# SCH_RP2040_Ucompute_V1_2_2025-10-13.net
KiCad netlist of a schematic drawn in EasyEDA
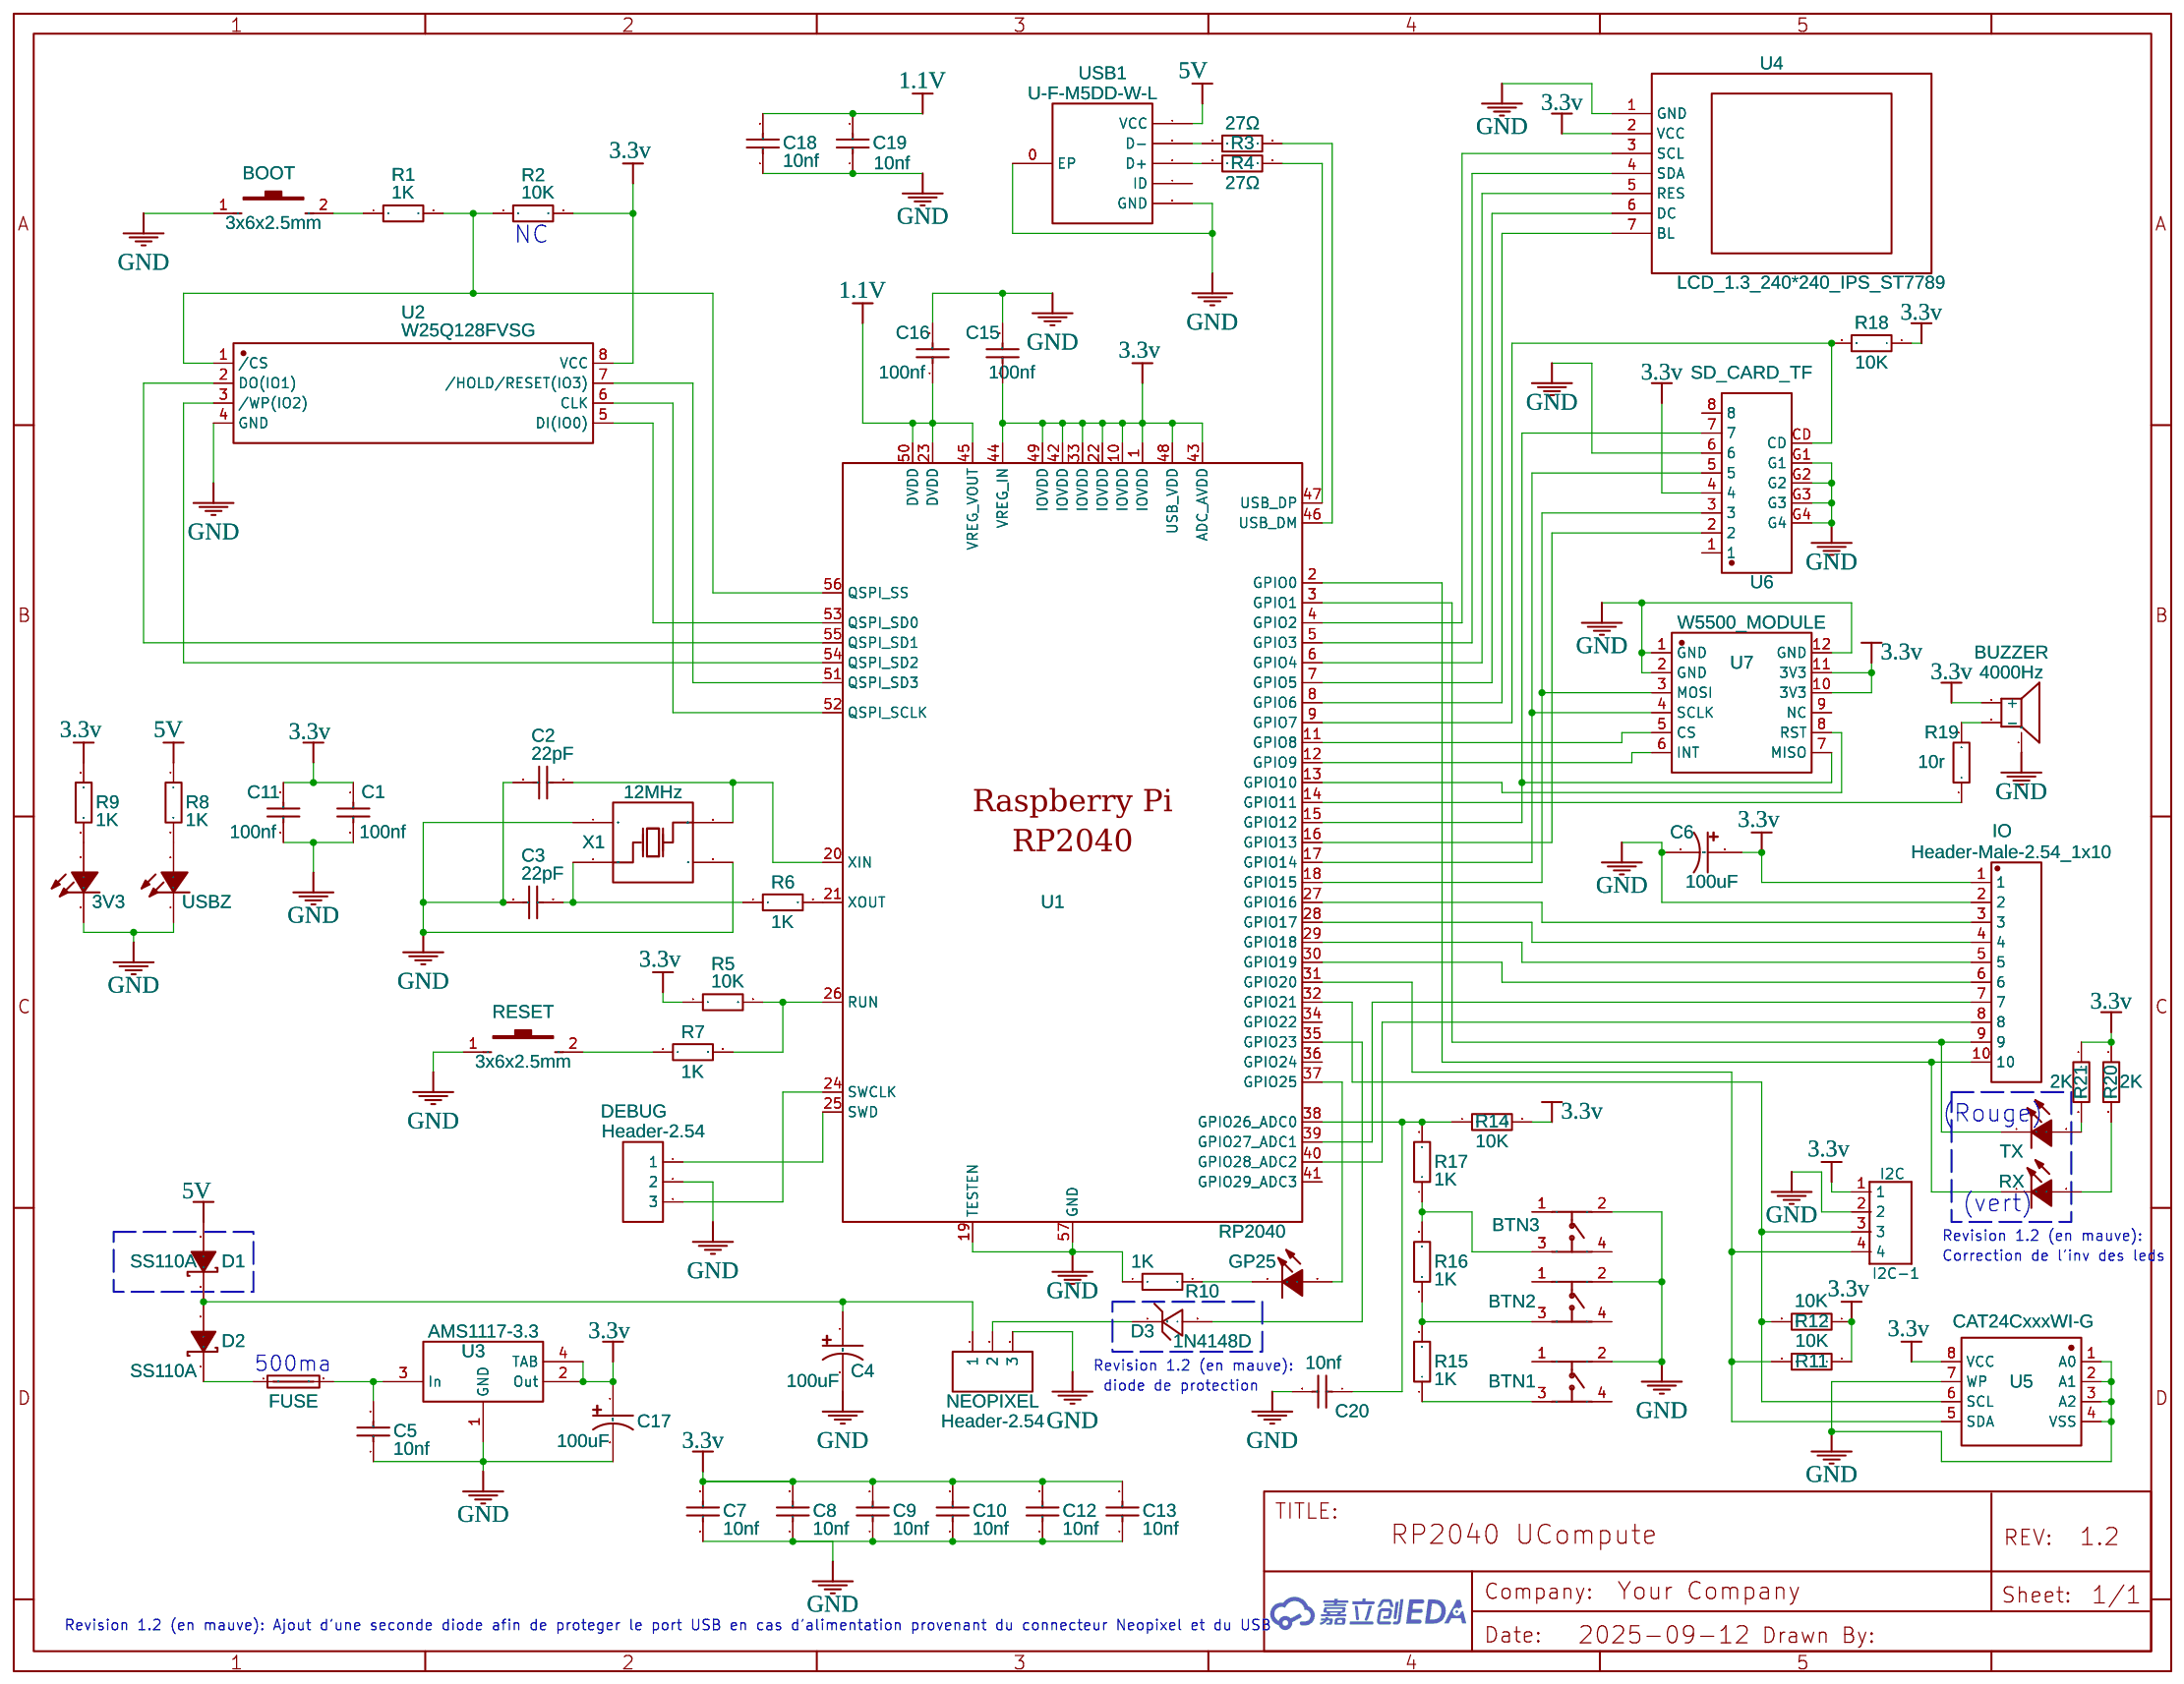
[diagram p0: schematic sheet]

(export (version "E")
  (design (tool "Eeschema 10.0.6"))
  (components
    (comp (ref "3V3")
      (value "XL-1206QPC")
      (fields (field (name "Manufacturer") "LCSC"))
      (libsource (lib "") (part "XL-1206QPC"))
    )
    (comp (ref "BOOT")
      (value "3x6x2.5mm")
      (fields (field (name "Manufacturer") "ReliaPro"))
      (libsource (lib "") (part "3x6x2.5mm_1"))
    )
    (comp (ref "BTN1")
      (value "TC-1102-A-J-R")
      (fields (field (name "Manufacturer") "XKB Connectivity(中国星坤)"))
      (libsource (lib "") (part "TC-1102-A-J-R"))
    )
    (comp (ref "BTN2")
      (value "TC-1102-A-J-R")
      (fields (field (name "Manufacturer") "XKB Connectivity(中国星坤)"))
      (libsource (lib "") (part "TC-1102-A-J-R"))
    )
    (comp (ref "BTN3")
      (value "TC-1102-A-J-R")
      (fields (field (name "Manufacturer") "XKB Connectivity(中国星坤)"))
      (libsource (lib "") (part "TC-1102-A-J-R"))
    )
    (comp (ref "BUZZER")
      (value "4000Hz")
      (fields (field (name "Manufacturer Part") "MLT-5030") (field (name "Manufacturer") "华能"))
      (libsource (lib "") (part "MLT-5030"))
    )
    (comp (ref "C1")
      (value "100nf")
      (fields (field (name "Manufacturer Part") "0805CG220J500NT") (field (name "Manufacturer") "FH"))
      (libsource (lib "") (part "0805CG220J500NT_1"))
    )
    (comp (ref "C2")
      (value "22pF")
      (fields (field (name "Manufacturer Part") "0805CG220J500NT") (field (name "Manufacturer") "FH"))
      (libsource (lib "") (part "0805CG220J500NT_3"))
    )
    (comp (ref "C3")
      (value "22pF")
      (fields (field (name "Manufacturer Part") "0805CG220J500NT") (field (name "Manufacturer") "FH"))
      (libsource (lib "") (part "0805CG220J500NT_3"))
    )
    (comp (ref "C4")
      (value "100uF")
      (fields
        (field (name "Manufacturer Part") "TLJA107M010R1400")
        (field (name "Manufacturer") "Kyocera AVX")
      )
      (libsource (lib "") (part "TLJA107M010R1400_1"))
    )
    (comp (ref "C5")
      (value "10nf")
      (fields (field (name "Manufacturer Part") "0805CG220J500NT") (field (name "Manufacturer") "FH"))
      (libsource (lib "") (part "0805CG220J500NT"))
    )
    (comp (ref "C6")
      (value "100uF")
      (fields
        (field (name "Manufacturer Part") "TLJA107M010R1400")
        (field (name "Manufacturer") "Kyocera AVX")
      )
      (libsource (lib "") (part "TLJA107M010R1400"))
    )
    (comp (ref "C7")
      (value "10nf")
      (fields (field (name "Manufacturer Part") "0805CG220J500NT") (field (name "Manufacturer") "FH"))
      (libsource (lib "") (part "0805CG220J500NT"))
    )
    (comp (ref "C8")
      (value "10nf")
      (fields (field (name "Manufacturer Part") "0805CG220J500NT") (field (name "Manufacturer") "FH"))
      (libsource (lib "") (part "0805CG220J500NT"))
    )
    (comp (ref "C9")
      (value "10nf")
      (fields (field (name "Manufacturer Part") "0805CG220J500NT") (field (name "Manufacturer") "FH"))
      (libsource (lib "") (part "0805CG220J500NT"))
    )
    (comp (ref "C10")
      (value "10nf")
      (fields (field (name "Manufacturer Part") "0805CG220J500NT") (field (name "Manufacturer") "FH"))
      (libsource (lib "") (part "0805CG220J500NT"))
    )
    (comp (ref "C11")
      (value "100nf")
      (fields (field (name "Manufacturer Part") "0805CG220J500NT") (field (name "Manufacturer") "FH"))
      (libsource (lib "") (part "0805CG220J500NT"))
    )
    (comp (ref "C12")
      (value "10nf")
      (fields (field (name "Manufacturer Part") "0805CG220J500NT") (field (name "Manufacturer") "FH"))
      (libsource (lib "") (part "0805CG220J500NT"))
    )
    (comp (ref "C13")
      (value "10nf")
      (fields (field (name "Manufacturer Part") "0805CG220J500NT") (field (name "Manufacturer") "FH"))
      (libsource (lib "") (part "0805CG220J500NT"))
    )
    (comp (ref "C15")
      (value "100nf")
      (fields (field (name "Manufacturer Part") "0805CG220J500NT") (field (name "Manufacturer") "FH"))
      (libsource (lib "") (part "0805CG220J500NT"))
    )
    (comp (ref "C16")
      (value "100nf")
      (fields (field (name "Manufacturer Part") "0805CG220J500NT") (field (name "Manufacturer") "FH"))
      (libsource (lib "") (part "0805CG220J500NT"))
    )
    (comp (ref "C17")
      (value "100uF")
      (fields
        (field (name "Manufacturer Part") "TLJA107M010R1400")
        (field (name "Manufacturer") "Kyocera AVX")
      )
      (libsource (lib "") (part "TLJA107M010R1400_1"))
    )
    (comp (ref "C18")
      (value "10nf")
      (fields (field (name "Manufacturer Part") "0805CG220J500NT") (field (name "Manufacturer") "FH"))
      (libsource (lib "") (part "0805CG220J500NT"))
    )
    (comp (ref "C19")
      (value "10nf")
      (fields (field (name "Manufacturer Part") "0805CG220J500NT") (field (name "Manufacturer") "FH"))
      (libsource (lib "") (part "0805CG220J500NT"))
    )
    (comp (ref "C20")
      (value "10nf")
      (fields (field (name "Manufacturer Part") "0805CG220J500NT") (field (name "Manufacturer") "FH"))
      (libsource (lib "") (part "0805CG220J500NT_2"))
    )
    (comp (ref "D1")
      (value "SS110A")
      (fields (field (name "Manufacturer") "Yangzhou Yangjie Elec Tech"))
      (libsource (lib "") (part "SS110A"))
    )
    (comp (ref "D2")
      (value "SS110A")
      (fields (field (name "Manufacturer") "Yangzhou Yangjie Elec Tech"))
      (libsource (lib "") (part "SS110A"))
    )
    (comp (ref "D3") (value "1N4148D") (libsource (lib "") (part "1N4148D")))
    (comp (ref "DEBUG")
      (value "Header-2.54")
      (fields (field (name "Manufacturer Part") "2.54-1*3P针") (field (name "Manufacturer") "BOOMELE(博穆精密)"))
      (libsource (lib "") (part "Header-Male-2.54_1x3"))
    )
    (comp (ref "FUSE")
      (value "FUSE1206")
      (fields (field (name "Manufacturer Part") "D22051903536_fuse1206"))
      (libsource (lib "") (part "D22051903536_FUSE1206"))
    )
    (comp (ref "GP25")
      (value "XL-1206QPC")
      (fields (field (name "Manufacturer") "LCSC"))
      (libsource (lib "") (part "XL-1206QPC_4"))
    )
    (comp (ref "I2C-1") (value "I2C") (libsource (lib "") (part "Unknown_941_-225")))
    (comp (ref "IO")
      (value "Header-Male-2.54_1x10")
      (fields (field (name "Manufacturer Part") "2.54-1*10P针") (field (name "Manufacturer") "BOOMELE(博穆精密)"))
      (libsource (lib "") (part "Header-Male-2.54_1x10"))
    )
    (comp (ref "NEOPIXEL")
      (value "Header-2.54")
      (fields (field (name "Manufacturer Part") "2.54-1*3P针") (field (name "Manufacturer") "BOOMELE(博穆精密)"))
      (libsource (lib "") (part "Header-Male-2.54_1x3_1"))
    )
    (comp (ref "R1")
      (value "1K")
      (fields (field (name "Manufacturer Part") "RC0805DR-071KL") (field (name "Manufacturer") "YAGEO(国巨)"))
      (libsource (lib "") (part "RC0805DR-071KL_2"))
    )
    (comp (ref "R2")
      (value "10K")
      (fields (field (name "Manufacturer Part") "RC0805DR-071KL") (field (name "Manufacturer") "YAGEO(国巨)"))
      (libsource (lib "") (part "RC0805DR-071KL_2"))
    )
    (comp (ref "R3")
      (value "27Ω")
      (fields (field (name "Manufacturer Part") "RC0805DR-071KL") (field (name "Manufacturer") "YAGEO(国巨)"))
      (libsource (lib "") (part "RC0805DR-071KL_2"))
    )
    (comp (ref "R4")
      (value "27Ω")
      (fields (field (name "Manufacturer Part") "RC0805DR-071KL") (field (name "Manufacturer") "YAGEO(国巨)"))
      (libsource (lib "") (part "RC0805DR-071KL_2"))
    )
    (comp (ref "R5")
      (value "10K")
      (fields (field (name "Manufacturer Part") "RC0805DR-071KL") (field (name "Manufacturer") "YAGEO(国巨)"))
      (libsource (lib "") (part "RC0805DR-071KL_2"))
    )
    (comp (ref "R6")
      (value "1K")
      (fields (field (name "Manufacturer Part") "RC0805DR-071KL") (field (name "Manufacturer") "YAGEO(国巨)"))
      (libsource (lib "") (part "RC0805DR-071KL_2"))
    )
    (comp (ref "R7")
      (value "1K")
      (fields (field (name "Manufacturer Part") "RC0805DR-071KL") (field (name "Manufacturer") "YAGEO(国巨)"))
      (libsource (lib "") (part "RC0805DR-071KL_2"))
    )
    (comp (ref "R8")
      (value "1K")
      (fields (field (name "Manufacturer Part") "RC0805DR-071KL") (field (name "Manufacturer") "YAGEO(国巨)"))
      (libsource (lib "") (part "RC0805DR-071KL_3"))
    )
    (comp (ref "R9")
      (value "1K")
      (fields (field (name "Manufacturer Part") "RC0805DR-071KL") (field (name "Manufacturer") "YAGEO(国巨)"))
      (libsource (lib "") (part "RC0805DR-071KL_3"))
    )
    (comp (ref "R10")
      (value "1K")
      (fields (field (name "Manufacturer Part") "RC0805DR-071KL") (field (name "Manufacturer") "YAGEO(国巨)"))
      (libsource (lib "") (part "RC0805DR-071KL_2"))
    )
    (comp (ref "R11")
      (value "10K")
      (fields (field (name "Manufacturer Part") "RC0805DR-071KL") (field (name "Manufacturer") "YAGEO(国巨)"))
      (libsource (lib "") (part "RC0805DR-071KL_1"))
    )
    (comp (ref "R12")
      (value "10K")
      (fields (field (name "Manufacturer Part") "RC0805DR-071KL") (field (name "Manufacturer") "YAGEO(国巨)"))
      (libsource (lib "") (part "RC0805DR-071KL_1"))
    )
    (comp (ref "R14")
      (value "10K")
      (fields (field (name "Manufacturer Part") "RC0805DR-071KL") (field (name "Manufacturer") "YAGEO(国巨)"))
      (libsource (lib "") (part "RC0805DR-071KL_2"))
    )
    (comp (ref "R15")
      (value "1K")
      (fields (field (name "Manufacturer Part") "RC0805DR-071KL") (field (name "Manufacturer") "YAGEO(国巨)"))
      (libsource (lib "") (part "RC0805DR-071KL"))
    )
    (comp (ref "R16")
      (value "1K")
      (fields (field (name "Manufacturer Part") "RC0805DR-071KL") (field (name "Manufacturer") "YAGEO(国巨)"))
      (libsource (lib "") (part "RC0805DR-071KL"))
    )
    (comp (ref "R17")
      (value "1K")
      (fields (field (name "Manufacturer Part") "RC0805DR-071KL") (field (name "Manufacturer") "YAGEO(国巨)"))
      (libsource (lib "") (part "RC0805DR-071KL"))
    )
    (comp (ref "R18")
      (value "10K")
      (fields (field (name "Manufacturer Part") "RC0805DR-071KL") (field (name "Manufacturer") "YAGEO(国巨)"))
      (libsource (lib "") (part "RC0805DR-071KL_1"))
    )
    (comp (ref "R19")
      (value "10r")
      (fields (field (name "Manufacturer Part") "RC0805DR-071KL") (field (name "Manufacturer") "YAGEO(国巨)"))
      (libsource (lib "") (part "RC0805DR-071KL"))
    )
    (comp (ref "R20")
      (value "2K")
      (fields (field (name "Manufacturer Part") "RC0805DR-071KL") (field (name "Manufacturer") "YAGEO(国巨)"))
      (libsource (lib "") (part "RC0805DR-071KL_3"))
    )
    (comp (ref "R21")
      (value "2K")
      (fields (field (name "Manufacturer Part") "RC0805DR-071KL") (field (name "Manufacturer") "YAGEO(国巨)"))
      (libsource (lib "") (part "RC0805DR-071KL_3"))
    )
    (comp (ref "RESET")
      (value "3x6x2.5mm")
      (fields (field (name "Manufacturer") "ReliaPro"))
      (libsource (lib "") (part "3x6x2.5mm"))
    )
    (comp (ref "RX1")
      (value "RX")
      (fields (field (name "Manufacturer Part") "XL-1206QPC") (field (name "Manufacturer") "LCSC"))
      (libsource (lib "") (part "XL-1206QPC_1"))
    )
    (comp (ref "TX1")
      (value "TX")
      (fields (field (name "Manufacturer Part") "XL-1206QPC") (field (name "Manufacturer") "LCSC"))
      (libsource (lib "") (part "XL-1206QPC_3"))
    )
    (comp (ref "U1")
      (value "RP2040")
      (fields (field (name "Manufacturer") "Raspberry Pi(树莓派)"))
      (libsource (lib "") (part "RP2040"))
    )
    (comp (ref "U2") (value "W25Q128FVSG") (libsource (lib "") (part "W25Q128FVSG")))
    (comp (ref "U3")
      (value "AMS1117-3.3")
      (fields (field (name "Manufacturer Part") "AMS1117-5.0") (field (name "Manufacturer") "SK"))
      (libsource (lib "") (part "AMS1117-5.0_C165483"))
    )
    (comp (ref "U4")
      (value "LCD_1.3_240*240_IPS_ST7789")
      (libsource (lib "") (part "LCD_1.3_240*240_IPS_ST7789"))
    )
    (comp (ref "U5") (value "CAT24CxxxWI-G") (libsource (lib "") (part "CAT24C256WI-G")))
    (comp (ref "U6")
      (value "SD_CARD_TF")
      (fields (field (name "Manufacturer Part") "SD_Card_TF"))
      (libsource (lib "") (part "SD_CARD_TF"))
    )
    (comp (ref "U7") (value "W5500_MODULE") (libsource (lib "") (part "W5500_MODULE")))
    (comp (ref "USB1")
      (value "U-F-M5DD-W-L")
      (fields (field (name "Manufacturer") "韩国韩荣"))
      (libsource (lib "") (part "U-F-M5DD-W-L"))
    )
    (comp (ref "USBZ")
      (value "XL-1206QPC")
      (fields (field (name "Manufacturer") "LCSC"))
      (libsource (lib "") (part "XL-1206QPC_2"))
    )
    (comp (ref "X1")
      (value "12MHz")
      (fields
        (field (name "Manufacturer Part") "TSX-3225 12MHz 20pF 30ppm")
        (field (name "Manufacturer") "EPSON")
      )
      (libsource (lib "") (part "TSX-3225 12MHz 20pF 30ppm"))
    )
  )
  (nets
    (net (code "1") (name "1.1V") (class "Default")
      (node (ref "C16") (pin "1") (pinfunction "1_1") (pintype "input"))
      (node (ref "C18") (pin "2") (pinfunction "2_2") (pintype "input"))
      (node (ref "C19") (pin "2") (pinfunction "2_2") (pintype "input"))
      (node (ref "U1") (pin "23") (pinfunction "DVDD_23") (pintype "bidirectional"))
      (node (ref "U1") (pin "45") (pinfunction "VREG_VOUT_45") (pintype "bidirectional"))
      (node (ref "U1") (pin "50") (pinfunction "DVDD_50") (pintype "bidirectional"))
    )
    (net (code "2") (name "3.3v") (class "Default")
      (node (ref "BUZZER") (pin "2") (pinfunction "+_2") (pintype "unspecified"))
      (node (ref "C1") (pin "1") (pinfunction "1_1") (pintype "input"))
      (node (ref "C10") (pin "2") (pinfunction "2_2") (pintype "input"))
      (node (ref "C11") (pin "2") (pinfunction "2_2") (pintype "input"))
      (node (ref "C12") (pin "2") (pinfunction "2_2") (pintype "input"))
      (node (ref "C13") (pin "2") (pinfunction "2_2") (pintype "input"))
      (node (ref "C15") (pin "1") (pinfunction "1_1") (pintype "input"))
      (node (ref "C17") (pin "1") (pinfunction "1_1") (pintype "unspecified"))
      (node (ref "C6") (pin "1") (pinfunction "1_1") (pintype "unspecified"))
      (node (ref "C7") (pin "2") (pinfunction "2_2") (pintype "input"))
      (node (ref "C8") (pin "2") (pinfunction "2_2") (pintype "input"))
      (node (ref "C9") (pin "2") (pinfunction "2_2") (pintype "input"))
      (node (ref "I2C-1") (pin "1") (pinfunction "1_1") (pintype "bidirectional"))
      (node (ref "IO") (pin "1") (pinfunction "1_1") (pintype "unspecified"))
      (node (ref "R11") (pin "1") (pinfunction "1_1") (pintype "unspecified"))
      (node (ref "R12") (pin "1") (pinfunction "1_1") (pintype "unspecified"))
      (node (ref "R14") (pin "2") (pinfunction "2_2") (pintype "unspecified"))
      (node (ref "R18") (pin "1") (pinfunction "1_1") (pintype "unspecified"))
      (node (ref "R2") (pin "2") (pinfunction "2_2") (pintype "unspecified"))
      (node (ref "R20") (pin "1") (pinfunction "1_1") (pintype "unspecified"))
      (node (ref "R21") (pin "1") (pinfunction "1_1") (pintype "unspecified"))
      (node (ref "R5") (pin "1") (pinfunction "1_1") (pintype "unspecified"))
      (node (ref "R9") (pin "1") (pinfunction "1_1") (pintype "unspecified"))
      (node (ref "U1") (pin "1") (pinfunction "IOVDD_1") (pintype "bidirectional"))
      (node (ref "U1") (pin "10") (pinfunction "IOVDD_10") (pintype "bidirectional"))
      (node (ref "U1") (pin "22") (pinfunction "IOVDD_22") (pintype "bidirectional"))
      (node (ref "U1") (pin "33") (pinfunction "IOVDD_33") (pintype "bidirectional"))
      (node (ref "U1") (pin "42") (pinfunction "IOVDD_42") (pintype "bidirectional"))
      (node (ref "U1") (pin "43") (pinfunction "ADC_AVDD_43") (pintype "bidirectional"))
      (node (ref "U1") (pin "44") (pinfunction "VREG_IN_44") (pintype "bidirectional"))
      (node (ref "U1") (pin "48") (pinfunction "USB_VDD_48") (pintype "bidirectional"))
      (node (ref "U1") (pin "49") (pinfunction "IOVDD_49") (pintype "bidirectional"))
      (node (ref "U2") (pin "8") (pinfunction "VCC_8") (pintype "unspecified"))
      (node (ref "U3") (pin "2") (pinfunction "Out_2") (pintype "unspecified"))
      (node (ref "U3") (pin "4") (pinfunction "TAB_4") (pintype "unspecified"))
      (node (ref "U4") (pin "2") (pinfunction "VCC_2") (pintype "unspecified"))
      (node (ref "U5") (pin "8") (pinfunction "VCC_8") (pintype "unspecified"))
      (node (ref "U6") (pin "4") (pinfunction "4_4") (pintype "unspecified"))
      (node (ref "U7") (pin "10") (pinfunction "3V3_10") (pintype "unspecified"))
      (node (ref "U7") (pin "11") (pinfunction "3V3_11") (pintype "unspecified"))
    )
    (net (code "3") (name "5V") (class "Default")
      (node (ref "D2") (pin "2") (pinfunction "A_2") (pintype "unspecified"))
      (node (ref "R8") (pin "1") (pinfunction "1_1") (pintype "unspecified"))
      (node (ref "USB1") (pin "1") (pinfunction "VCC_1") (pintype "input"))
    )
    (net (code "4") (name "GND") (class "Default")
      (node (ref "3V3") (pin "1") (pinfunction "K_1") (pintype "unspecified"))
      (node (ref "BOOT") (pin "1") (pinfunction "1_1") (pintype "input"))
      (node (ref "BTN1") (pin "2") (pinfunction "2_2") (pintype "unspecified"))
      (node (ref "BTN2") (pin "2") (pinfunction "2_2") (pintype "unspecified"))
      (node (ref "BTN3") (pin "2") (pinfunction "2_2") (pintype "unspecified"))
      (node (ref "BUZZER") (pin "1") (pinfunction "NC_1") (pintype "unspecified"))
      (node (ref "C1") (pin "2") (pinfunction "2_2") (pintype "input"))
      (node (ref "C10") (pin "1") (pinfunction "1_1") (pintype "input"))
      (node (ref "C11") (pin "1") (pinfunction "1_1") (pintype "input"))
      (node (ref "C12") (pin "1") (pinfunction "1_1") (pintype "input"))
      (node (ref "C13") (pin "1") (pinfunction "1_1") (pintype "input"))
      (node (ref "C15") (pin "2") (pinfunction "2_2") (pintype "input"))
      (node (ref "C16") (pin "2") (pinfunction "2_2") (pintype "input"))
      (node (ref "C17") (pin "2") (pinfunction "2_2") (pintype "unspecified"))
      (node (ref "C18") (pin "1") (pinfunction "1_1") (pintype "input"))
      (node (ref "C19") (pin "1") (pinfunction "1_1") (pintype "input"))
      (node (ref "C2") (pin "1") (pinfunction "1_1") (pintype "input"))
      (node (ref "C20") (pin "2") (pinfunction "2_2") (pintype "input"))
      (node (ref "C3") (pin "1") (pinfunction "1_1") (pintype "input"))
      (node (ref "C4") (pin "2") (pinfunction "2_2") (pintype "unspecified"))
      (node (ref "C5") (pin "1") (pinfunction "1_1") (pintype "input"))
      (node (ref "C6") (pin "2") (pinfunction "2_2") (pintype "unspecified"))
      (node (ref "C7") (pin "1") (pinfunction "1_1") (pintype "input"))
      (node (ref "C8") (pin "1") (pinfunction "1_1") (pintype "input"))
      (node (ref "C9") (pin "1") (pinfunction "1_1") (pintype "input"))
      (node (ref "DEBUG") (pin "2") (pinfunction "2_2") (pintype "input"))
      (node (ref "I2C-1") (pin "2") (pinfunction "2_2") (pintype "bidirectional"))
      (node (ref "IO") (pin "2") (pinfunction "2_2") (pintype "unspecified"))
      (node (ref "NEOPIXEL") (pin "3") (pinfunction "3_3") (pintype "input"))
      (node (ref "R10") (pin "1") (pinfunction "1_1") (pintype "unspecified"))
      (node (ref "RESET") (pin "1") (pinfunction "1_1") (pintype "input"))
      (node (ref "U1") (pin "19") (pinfunction "TESTEN_19") (pintype "unspecified"))
      (node (ref "U1") (pin "57") (pinfunction "GND_57") (pintype "bidirectional"))
      (node (ref "U2") (pin "4") (pinfunction "GND_4") (pintype "unspecified"))
      (node (ref "U3") (pin "1") (pinfunction "GND_1") (pintype "unspecified"))
      (node (ref "U4") (pin "1") (pinfunction "GND_1") (pintype "unspecified"))
      (node (ref "U5") (pin "1") (pinfunction "A0_1") (pintype "unspecified"))
      (node (ref "U5") (pin "2") (pinfunction "A1_2") (pintype "unspecified"))
      (node (ref "U5") (pin "3") (pinfunction "A2_3") (pintype "unspecified"))
      (node (ref "U5") (pin "4") (pinfunction "VSS_4") (pintype "unspecified"))
      (node (ref "U5") (pin "7") (pinfunction "WP_7") (pintype "unspecified"))
      (node (ref "U6") (pin "6") (pinfunction "6_6") (pintype "unspecified"))
      (node (ref "U6") (pin "G1") (pinfunction "G1_G1") (pintype "unspecified"))
      (node (ref "U6") (pin "G2") (pinfunction "G2_G2") (pintype "unspecified"))
      (node (ref "U6") (pin "G3") (pinfunction "G3_G3") (pintype "unspecified"))
      (node (ref "U6") (pin "G4") (pinfunction "G4_G4") (pintype "unspecified"))
      (node (ref "U7") (pin "1") (pinfunction "GND_1") (pintype "unspecified"))
      (node (ref "U7") (pin "12") (pinfunction "GND_12") (pintype "unspecified"))
      (node (ref "U7") (pin "2") (pinfunction "GND_2") (pintype "unspecified"))
      (node (ref "USB1") (pin "0") (pinfunction "EP_0") (pintype "unspecified"))
      (node (ref "USB1") (pin "5") (pinfunction "GND_5") (pintype "input"))
      (node (ref "USBZ") (pin "1") (pinfunction "K_1") (pintype "unspecified"))
      (node (ref "X1") (pin "2") (pinfunction "NC_2") (pintype "input"))
      (node (ref "X1") (pin "4") (pinfunction "NC_4") (pintype "input"))
    )
    (net (code "5") (name "Net-(3V3-A)") (class "Default")
      (node (ref "3V3") (pin "2") (pinfunction "A_2") (pintype "unspecified"))
      (node (ref "R9") (pin "2") (pinfunction "2_2") (pintype "unspecified"))
    )
    (net (code "6") (name "Net-(BOOT-Pad2)") (class "Default")
      (node (ref "BOOT") (pin "2") (pinfunction "2_2") (pintype "input"))
      (node (ref "R1") (pin "1") (pinfunction "1_1") (pintype "unspecified"))
    )
    (net (code "7") (name "Net-(BTN1-Pad3)") (class "Default")
      (node (ref "BTN1") (pin "3") (pinfunction "3_3") (pintype "unspecified"))
      (node (ref "R15") (pin "1") (pinfunction "1_1") (pintype "unspecified"))
    )
    (net (code "8") (name "Net-(BTN2-Pad3)") (class "Default")
      (node (ref "BTN2") (pin "3") (pinfunction "3_3") (pintype "unspecified"))
      (node (ref "R15") (pin "2") (pinfunction "2_2") (pintype "unspecified"))
      (node (ref "R16") (pin "1") (pinfunction "1_1") (pintype "unspecified"))
    )
    (net (code "9") (name "Net-(BTN3-Pad3)") (class "Default")
      (node (ref "BTN3") (pin "3") (pinfunction "3_3") (pintype "unspecified"))
      (node (ref "R16") (pin "2") (pinfunction "2_2") (pintype "unspecified"))
      (node (ref "R17") (pin "1") (pinfunction "1_1") (pintype "unspecified"))
    )
    (net (code "10") (name "Net-(BUZZER--)") (class "Default")
      (node (ref "BUZZER") (pin "3") (pinfunction "-_3") (pintype "unspecified"))
      (node (ref "R19") (pin "2") (pinfunction "2_2") (pintype "unspecified"))
    )
    (net (code "11") (name "Net-(D1-A)") (class "Default")
      (node (ref "C4") (pin "1") (pinfunction "1_1") (pintype "unspecified"))
      (node (ref "D1") (pin "2") (pinfunction "A_2") (pintype "unspecified"))
      (node (ref "D2") (pin "1") (pinfunction "K_1") (pintype "unspecified"))
      (node (ref "NEOPIXEL") (pin "1") (pinfunction "1_1") (pintype "input"))
    )
    (net (code "12") (name "Net-(D1-K)") (class "Default")
      (node (ref "D1") (pin "1") (pinfunction "K_1") (pintype "unspecified"))
      (node (ref "FUSE") (pin "1") (pinfunction "1_1") (pintype "unspecified"))
    )
    (net (code "13") (name "Net-(D3-A)") (class "Default")
      (node (ref "D3") (pin "2") (pinfunction "A_2") (pintype "unspecified"))
      (node (ref "U1") (pin "35") (pinfunction "GPIO23_35") (pintype "bidirectional"))
    )
    (net (code "14") (name "Net-(D3-C)") (class "Default")
      (node (ref "D3") (pin "1") (pinfunction "C_1") (pintype "unspecified"))
      (node (ref "NEOPIXEL") (pin "2") (pinfunction "2_2") (pintype "input"))
    )
    (net (code "15") (name "Net-(GP25-A)") (class "Default")
      (node (ref "GP25") (pin "2") (pinfunction "A_2") (pintype "unspecified"))
      (node (ref "U1") (pin "37") (pinfunction "GPIO25_37") (pintype "bidirectional"))
    )
    (net (code "16") (name "Net-(GP25-K)") (class "Default")
      (node (ref "GP25") (pin "1") (pinfunction "K_1") (pintype "unspecified"))
      (node (ref "R10") (pin "2") (pinfunction "2_2") (pintype "unspecified"))
    )
    (net (code "17") (name "Net-(R7-Pad1)") (class "Default")
      (node (ref "R7") (pin "1") (pinfunction "1_1") (pintype "unspecified"))
      (node (ref "RESET") (pin "2") (pinfunction "2_2") (pintype "input"))
    )
    (net (code "18") (name "Net-(RX1-A)") (class "Default")
      (node (ref "R20") (pin "2") (pinfunction "2_2") (pintype "unspecified"))
      (node (ref "RX1") (pin "2") (pinfunction "A_2") (pintype "unspecified"))
    )
    (net (code "19") (name "Net-(RX1-K)") (class "Default")
      (node (ref "IO") (pin "10") (pinfunction "10_10") (pintype "unspecified"))
      (node (ref "RX1") (pin "1") (pinfunction "K_1") (pintype "unspecified"))
      (node (ref "U1") (pin "2") (pinfunction "GPIO0_2") (pintype "bidirectional"))
    )
    (net (code "20") (name "Net-(TX1-A)") (class "Default")
      (node (ref "R21") (pin "2") (pinfunction "2_2") (pintype "unspecified"))
      (node (ref "TX1") (pin "2") (pinfunction "A_2") (pintype "unspecified"))
    )
    (net (code "21") (name "Net-(TX1-K)") (class "Default")
      (node (ref "IO") (pin "9") (pinfunction "9_9") (pintype "unspecified"))
      (node (ref "TX1") (pin "1") (pinfunction "K_1") (pintype "unspecified"))
      (node (ref "U1") (pin "3") (pinfunction "GPIO1_3") (pintype "bidirectional"))
    )
    (net (code "22") (name "Net-(U1-GPIO2)") (class "Default")
      (node (ref "U1") (pin "4") (pinfunction "GPIO2_4") (pintype "bidirectional"))
      (node (ref "U4") (pin "3") (pinfunction "SCL_3") (pintype "unspecified"))
    )
    (net (code "23") (name "Net-(U1-GPIO3)") (class "Default")
      (node (ref "U1") (pin "5") (pinfunction "GPIO3_5") (pintype "bidirectional"))
      (node (ref "U4") (pin "4") (pinfunction "SDA_4") (pintype "unspecified"))
    )
    (net (code "24") (name "Net-(U1-GPIO4)") (class "Default")
      (node (ref "U1") (pin "6") (pinfunction "GPIO4_6") (pintype "bidirectional"))
      (node (ref "U4") (pin "5") (pinfunction "RES_5") (pintype "unspecified"))
    )
    (net (code "25") (name "Net-(U1-GPIO5)") (class "Default")
      (node (ref "U1") (pin "7") (pinfunction "GPIO5_7") (pintype "bidirectional"))
      (node (ref "U4") (pin "6") (pinfunction "DC_6") (pintype "unspecified"))
    )
    (net (code "26") (name "Net-(U1-GPIO6)") (class "Default")
      (node (ref "U1") (pin "8") (pinfunction "GPIO6_8") (pintype "bidirectional"))
      (node (ref "U4") (pin "7") (pinfunction "BL_7") (pintype "unspecified"))
    )
    (net (code "27") (name "Net-(U1-GPIO7)") (class "Default")
      (node (ref "R18") (pin "2") (pinfunction "2_2") (pintype "unspecified"))
      (node (ref "U1") (pin "9") (pinfunction "GPIO7_9") (pintype "bidirectional"))
      (node (ref "U6") (pin "CD") (pinfunction "CD_CD") (pintype "unspecified"))
    )
    (net (code "28") (name "Net-(U1-GPIO8)") (class "Default")
      (node (ref "U1") (pin "11") (pinfunction "GPIO8_11") (pintype "bidirectional"))
      (node (ref "U7") (pin "5") (pinfunction "CS_5") (pintype "unspecified"))
    )
    (net (code "29") (name "Net-(U1-GPIO9)") (class "Default")
      (node (ref "U1") (pin "12") (pinfunction "GPIO9_12") (pintype "bidirectional"))
      (node (ref "U7") (pin "6") (pinfunction "INT_6") (pintype "unspecified"))
    )
    (net (code "30") (name "Net-(U1-GPIO10)") (class "Default")
      (node (ref "U1") (pin "13") (pinfunction "GPIO10_13") (pintype "bidirectional"))
      (node (ref "U7") (pin "8") (pinfunction "RST_8") (pintype "unspecified"))
    )
    (net (code "31") (name "Net-(U1-GPIO11)") (class "Default")
      (node (ref "R19") (pin "1") (pinfunction "1_1") (pintype "unspecified"))
      (node (ref "U1") (pin "14") (pinfunction "GPIO11_14") (pintype "bidirectional"))
    )
    (net (code "32") (name "Net-(U1-GPIO12)") (class "Default")
      (node (ref "U1") (pin "15") (pinfunction "GPIO12_15") (pintype "bidirectional"))
      (node (ref "U6") (pin "7") (pinfunction "7_7") (pintype "unspecified"))
      (node (ref "U7") (pin "7") (pinfunction "MISO_7") (pintype "unspecified"))
    )
    (net (code "33") (name "Net-(U1-GPIO13)") (class "Default")
      (node (ref "U1") (pin "16") (pinfunction "GPIO13_16") (pintype "bidirectional"))
      (node (ref "U6") (pin "2") (pinfunction "2_2") (pintype "unspecified"))
    )
    (net (code "34") (name "Net-(U1-GPIO14)") (class "Default")
      (node (ref "U1") (pin "17") (pinfunction "GPIO14_17") (pintype "bidirectional"))
      (node (ref "U6") (pin "5") (pinfunction "5_5") (pintype "unspecified"))
      (node (ref "U7") (pin "4") (pinfunction "SCLK_4") (pintype "unspecified"))
    )
    (net (code "35") (name "Net-(U1-GPIO15)") (class "Default")
      (node (ref "U1") (pin "18") (pinfunction "GPIO15_18") (pintype "bidirectional"))
      (node (ref "U6") (pin "3") (pinfunction "3_3") (pintype "unspecified"))
      (node (ref "U7") (pin "3") (pinfunction "MOSI_3") (pintype "unspecified"))
    )
    (net (code "36") (name "Net-(U1-GPIO16)") (class "Default")
      (node (ref "IO") (pin "3") (pinfunction "3_3") (pintype "unspecified"))
      (node (ref "U1") (pin "27") (pinfunction "GPIO16_27") (pintype "bidirectional"))
    )
    (net (code "37") (name "Net-(U1-GPIO17)") (class "Default")
      (node (ref "IO") (pin "4") (pinfunction "4_4") (pintype "unspecified"))
      (node (ref "U1") (pin "28") (pinfunction "GPIO17_28") (pintype "bidirectional"))
    )
    (net (code "38") (name "Net-(U1-GPIO18)") (class "Default")
      (node (ref "IO") (pin "5") (pinfunction "5_5") (pintype "unspecified"))
      (node (ref "U1") (pin "29") (pinfunction "GPIO18_29") (pintype "bidirectional"))
    )
    (net (code "39") (name "Net-(U1-GPIO19)") (class "Default")
      (node (ref "IO") (pin "6") (pinfunction "6_6") (pintype "unspecified"))
      (node (ref "U1") (pin "30") (pinfunction "GPIO19_30") (pintype "bidirectional"))
    )
    (net (code "40") (name "Net-(U1-GPIO20)") (class "Default")
      (node (ref "I2C-1") (pin "4") (pinfunction "4_4") (pintype "bidirectional"))
      (node (ref "R11") (pin "2") (pinfunction "2_2") (pintype "unspecified"))
      (node (ref "U1") (pin "31") (pinfunction "GPIO20_31") (pintype "bidirectional"))
      (node (ref "U5") (pin "5") (pinfunction "SDA_5") (pintype "unspecified"))
    )
    (net (code "41") (name "Net-(U1-GPIO21)") (class "Default")
      (node (ref "I2C-1") (pin "3") (pinfunction "3_3") (pintype "bidirectional"))
      (node (ref "R12") (pin "2") (pinfunction "2_2") (pintype "unspecified"))
      (node (ref "U1") (pin "32") (pinfunction "GPIO21_32") (pintype "bidirectional"))
      (node (ref "U5") (pin "6") (pinfunction "SCL_6") (pintype "unspecified"))
    )
    (net (code "42") (name "Net-(U1-GPIO26_ADC0)") (class "Default")
      (node (ref "C20") (pin "1") (pinfunction "1_1") (pintype "input"))
      (node (ref "R14") (pin "1") (pinfunction "1_1") (pintype "unspecified"))
      (node (ref "R17") (pin "2") (pinfunction "2_2") (pintype "unspecified"))
      (node (ref "U1") (pin "38") (pinfunction "GPIO26_ADC0_38") (pintype "bidirectional"))
    )
    (net (code "43") (name "Net-(U1-GPIO27_ADC1)") (class "Default")
      (node (ref "IO") (pin "7") (pinfunction "7_7") (pintype "unspecified"))
      (node (ref "U1") (pin "39") (pinfunction "GPIO27_ADC1_39") (pintype "bidirectional"))
    )
    (net (code "44") (name "Net-(U1-GPIO28_ADC2)") (class "Default")
      (node (ref "IO") (pin "8") (pinfunction "8_8") (pintype "unspecified"))
      (node (ref "U1") (pin "40") (pinfunction "GPIO28_ADC2_40") (pintype "bidirectional"))
    )
    (net (code "45") (name "Net-(U1-QSPI_SCLK)") (class "Default")
      (node (ref "U1") (pin "52") (pinfunction "QSPI_SCLK_52") (pintype "output"))
      (node (ref "U2") (pin "6") (pinfunction "CLK_6") (pintype "unspecified"))
    )
    (net (code "46") (name "Net-(U1-QSPI_SD0)") (class "Default")
      (node (ref "U1") (pin "53") (pinfunction "QSPI_SD0_53") (pintype "bidirectional"))
      (node (ref "U2") (pin "5") (pinfunction "DI(IO0)_5") (pintype "unspecified"))
    )
    (net (code "47") (name "Net-(U1-QSPI_SD1)") (class "Default")
      (node (ref "U1") (pin "55") (pinfunction "QSPI_SD1_55") (pintype "bidirectional"))
      (node (ref "U2") (pin "2") (pinfunction "DO(IO1)_2") (pintype "unspecified"))
    )
    (net (code "48") (name "Net-(U1-QSPI_SD2)") (class "Default")
      (node (ref "U1") (pin "54") (pinfunction "QSPI_SD2_54") (pintype "bidirectional"))
      (node (ref "U2") (pin "3") (pinfunction "/WP(IO2)_3") (pintype "unspecified"))
    )
    (net (code "49") (name "Net-(U1-QSPI_SD3)") (class "Default")
      (node (ref "U1") (pin "51") (pinfunction "QSPI_SD3_51") (pintype "bidirectional"))
      (node (ref "U2") (pin "7") (pinfunction "/HOLD/RESET(IO3)_7") (pintype "unspecified"))
    )
    (net (code "50") (name "Net-(U1-QSPI_SS)") (class "Default")
      (node (ref "R1") (pin "2") (pinfunction "2_2") (pintype "unspecified"))
      (node (ref "R2") (pin "1") (pinfunction "1_1") (pintype "unspecified"))
      (node (ref "U1") (pin "56") (pinfunction "QSPI_SS_56") (pintype "bidirectional"))
      (node (ref "U2") (pin "1") (pinfunction "/CS_1") (pintype "unspecified"))
    )
    (net (code "51") (name "Net-(U1-RUN)") (class "Default")
      (node (ref "R5") (pin "2") (pinfunction "2_2") (pintype "unspecified"))
      (node (ref "R7") (pin "2") (pinfunction "2_2") (pintype "unspecified"))
      (node (ref "U1") (pin "26") (pinfunction "RUN_26") (pintype "input"))
    )
    (net (code "52") (name "Net-(U1-SWCLK)") (class "Default")
      (node (ref "DEBUG") (pin "3") (pinfunction "3_3") (pintype "input"))
      (node (ref "U1") (pin "24") (pinfunction "SWCLK_24") (pintype "output"))
    )
    (net (code "53") (name "Net-(U1-SWD)") (class "Default")
      (node (ref "DEBUG") (pin "1") (pinfunction "1_1") (pintype "input"))
      (node (ref "U1") (pin "25") (pinfunction "SWD_25") (pintype "bidirectional"))
    )
    (net (code "54") (name "Net-(U1-USB_DM)") (class "Default")
      (node (ref "R3") (pin "2") (pinfunction "2_2") (pintype "unspecified"))
      (node (ref "U1") (pin "46") (pinfunction "USB_DM_46") (pintype "bidirectional"))
    )
    (net (code "55") (name "Net-(U1-USB_DP)") (class "Default")
      (node (ref "R4") (pin "2") (pinfunction "2_2") (pintype "unspecified"))
      (node (ref "U1") (pin "47") (pinfunction "USB_DP_47") (pintype "bidirectional"))
    )
    (net (code "56") (name "Net-(U1-XIN)") (class "Default")
      (node (ref "C2") (pin "2") (pinfunction "2_2") (pintype "input"))
      (node (ref "U1") (pin "20") (pinfunction "XIN_20") (pintype "input"))
      (node (ref "X1") (pin "3") (pinfunction "OSC2_3") (pintype "input"))
    )
    (net (code "57") (name "Net-(U1-XOUT)") (class "Default")
      (node (ref "R6") (pin "2") (pinfunction "2_2") (pintype "unspecified"))
      (node (ref "U1") (pin "21") (pinfunction "XOUT_21") (pintype "unspecified"))
    )
    (net (code "58") (name "Net-(U3-In)") (class "Default")
      (node (ref "C5") (pin "2") (pinfunction "2_2") (pintype "input"))
      (node (ref "FUSE") (pin "2") (pinfunction "2_2") (pintype "unspecified"))
      (node (ref "U3") (pin "3") (pinfunction "In_3") (pintype "unspecified"))
    )
    (net (code "59") (name "Net-(USB1-D+)") (class "Default")
      (node (ref "R4") (pin "1") (pinfunction "1_1") (pintype "unspecified"))
      (node (ref "USB1") (pin "3") (pinfunction "D+_3") (pintype "input"))
    )
    (net (code "60") (name "Net-(USB1-D-)") (class "Default")
      (node (ref "R3") (pin "1") (pinfunction "1_1") (pintype "unspecified"))
      (node (ref "USB1") (pin "2") (pinfunction "D-_2") (pintype "input"))
    )
    (net (code "61") (name "Net-(USBZ-A)") (class "Default")
      (node (ref "R8") (pin "2") (pinfunction "2_2") (pintype "unspecified"))
      (node (ref "USBZ") (pin "2") (pinfunction "A_2") (pintype "unspecified"))
    )
    (net (code "62") (name "Net-(X1-OSC1)") (class "Default")
      (node (ref "C3") (pin "2") (pinfunction "2_2") (pintype "input"))
      (node (ref "R6") (pin "1") (pinfunction "1_1") (pintype "unspecified"))
      (node (ref "X1") (pin "1") (pinfunction "OSC1_1") (pintype "input"))
    )
    (net (code "63") (name "unconnected-(BTN1-Pad1)") (class "Default")
      (node (ref "BTN1") (pin "1") (pinfunction "1_1") (pintype "unspecified"))
    )
    (net (code "64") (name "unconnected-(BTN1-Pad4)") (class "Default")
      (node (ref "BTN1") (pin "4") (pinfunction "4_4") (pintype "unspecified"))
    )
    (net (code "65") (name "unconnected-(BTN2-Pad1)") (class "Default")
      (node (ref "BTN2") (pin "1") (pinfunction "1_1") (pintype "unspecified"))
    )
    (net (code "66") (name "unconnected-(BTN2-Pad4)") (class "Default")
      (node (ref "BTN2") (pin "4") (pinfunction "4_4") (pintype "unspecified"))
    )
    (net (code "67") (name "unconnected-(BTN3-Pad1)") (class "Default")
      (node (ref "BTN3") (pin "1") (pinfunction "1_1") (pintype "unspecified"))
    )
    (net (code "68") (name "unconnected-(BTN3-Pad4)") (class "Default")
      (node (ref "BTN3") (pin "4") (pinfunction "4_4") (pintype "unspecified"))
    )
    (net (code "69") (name "unconnected-(U1-GPIO22-Pad34)") (class "Default")
      (node (ref "U1") (pin "34") (pinfunction "GPIO22_34") (pintype "bidirectional"))
    )
    (net (code "70") (name "unconnected-(U1-GPIO24-Pad36)") (class "Default")
      (node (ref "U1") (pin "36") (pinfunction "GPIO24_36") (pintype "bidirectional"))
    )
    (net (code "71") (name "unconnected-(U1-GPIO29_ADC3-Pad41)") (class "Default")
      (node (ref "U1") (pin "41") (pinfunction "GPIO29_ADC3_41") (pintype "bidirectional"))
    )
    (net (code "72") (name "unconnected-(U6-Pad1)") (class "Default")
      (node (ref "U6") (pin "1") (pinfunction "1_1") (pintype "unspecified"))
    )
    (net (code "73") (name "unconnected-(U6-Pad8)") (class "Default")
      (node (ref "U6") (pin "8") (pinfunction "8_8") (pintype "unspecified"))
    )
    (net (code "74") (name "unconnected-(U7-NC-Pad9)") (class "Default")
      (node (ref "U7") (pin "9") (pinfunction "NC_9") (pintype "unspecified"))
    )
    (net (code "75") (name "unconnected-(USB1-ID-Pad4)") (class "Default")
      (node (ref "USB1") (pin "4") (pinfunction "ID_4") (pintype "input"))
    )
  )
)
